# Analog_Sense.net
KiCad netlist of a schematic drawn in Altium Designer
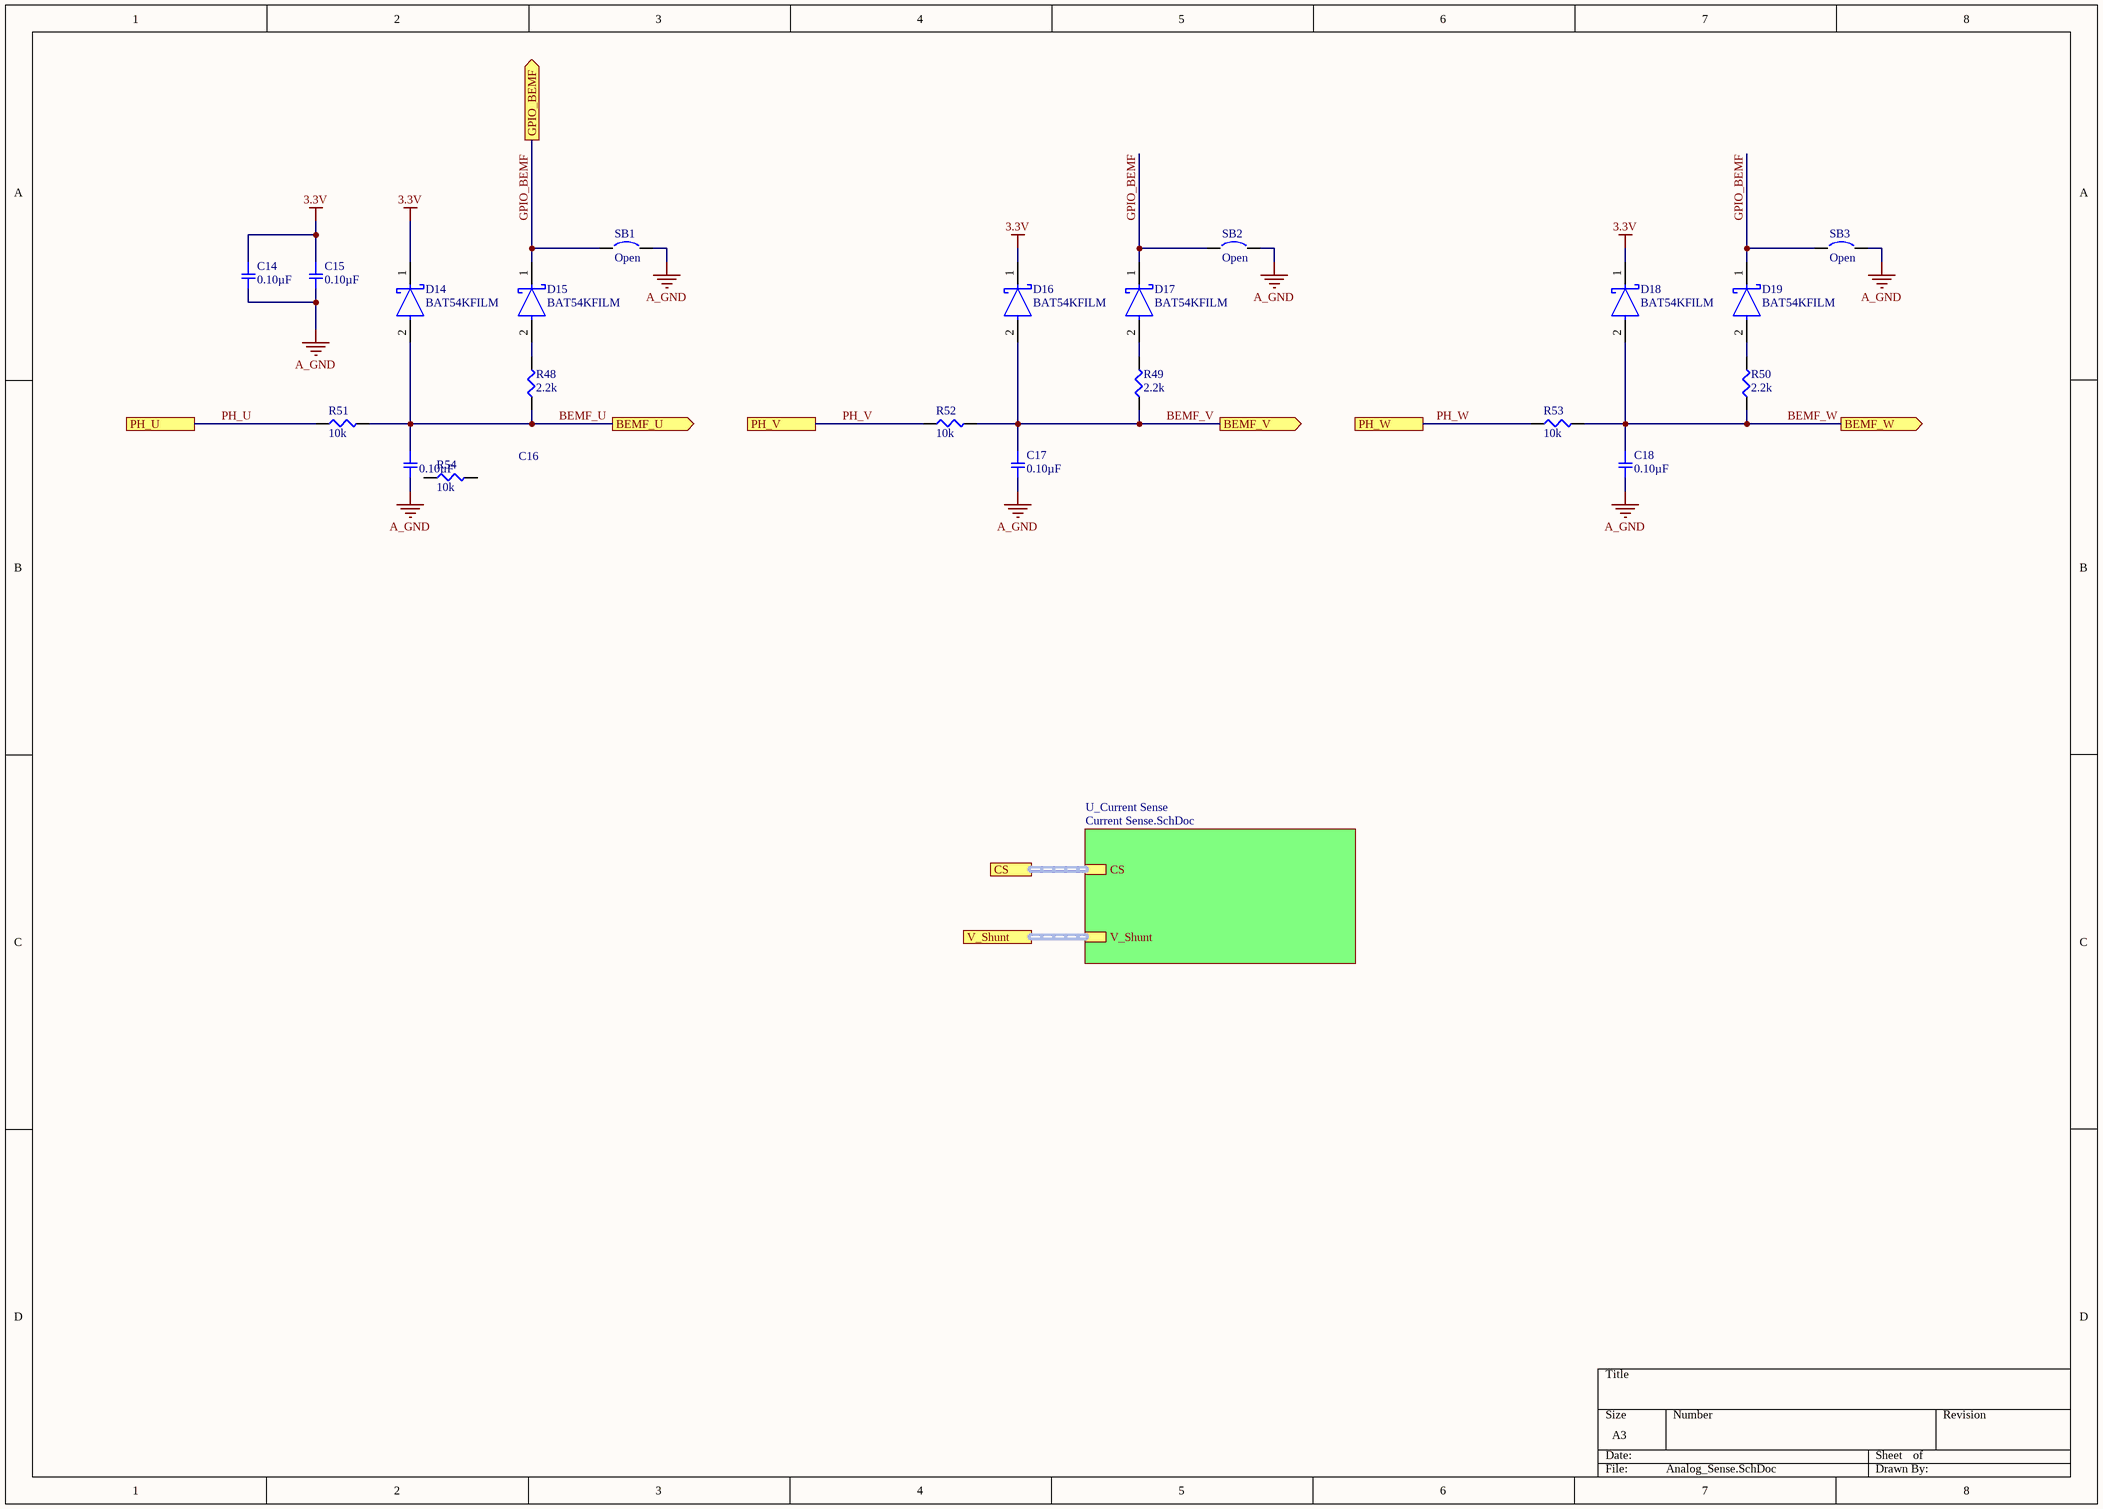
[diagram p0: Analog_Sense.SchDoc]

(export (version "E")
  (design (tool "Eeschema 10.0.6"))
  (components
    (comp (ref "C14")
      (value "0.10µF")
      (footprint "SMD-0805C")
      (description "CAP CER 0.1UF 50V X7R 0805")
      (fields
        (field (name "DIGI-KEY PART NUMBER") "490-11955-1-ND")
        (field (name "PART NUMBER") "GCD21BR71H104KA01L")
      )
      (libsource (lib "capacitor_murata_0805") (part "GCD21BR71H104KA01L"))
    )
    (comp (ref "C15")
      (value "0.10µF")
      (footprint "SMD-0805C")
      (description "CAP CER 0.1UF 50V X7R 0805")
      (fields
        (field (name "DIGI-KEY PART NUMBER") "490-11955-1-ND")
        (field (name "PART NUMBER") "GCD21BR71H104KA01L")
      )
      (libsource (lib "capacitor_murata_0805") (part "GCD21BR71H104KA01L"))
    )
    (comp (ref "C16")
      (value "0.10µF")
      (footprint "SMD-0805C")
      (description "CAP CER 0.1UF 50V X7R 0805")
      (fields
        (field (name "DIGI-KEY PART NUMBER") "490-11955-1-ND")
        (field (name "PART NUMBER") "GCD21BR71H104KA01L")
      )
      (libsource (lib "capacitor_murata_0805") (part "GCD21BR71H104KA01L"))
    )
    (comp (ref "C17")
      (value "0.10µF")
      (footprint "SMD-0805C")
      (description "CAP CER 0.1UF 50V X7R 0805")
      (fields
        (field (name "DIGI-KEY PART NUMBER") "490-11955-1-ND")
        (field (name "PART NUMBER") "GCD21BR71H104KA01L")
      )
      (libsource (lib "capacitor_murata_0805") (part "GCD21BR71H104KA01L"))
    )
    (comp (ref "C18")
      (value "0.10µF")
      (footprint "SMD-0805C")
      (description "CAP CER 0.1UF 50V X7R 0805")
      (fields
        (field (name "DIGI-KEY PART NUMBER") "490-11955-1-ND")
        (field (name "PART NUMBER") "GCD21BR71H104KA01L")
      )
      (libsource (lib "capacitor_murata_0805") (part "GCD21BR71H104KA01L"))
    )
    (comp (ref "D14")
      (value "BAT54KFILM")
      (footprint "FP-SOD-523-MFG")
      (description "DIODE SCHOTTKY 40V 300MA SOD523")
      (fields
        (field (name "OCTOPART") "https://octopart.com/bat54kfilm-stmicroelectronics-39618022")
        (field (name "MANUFACTURER") "STMicroelectronics")
      )
      (libsource (lib "Altium Content Vault") (part "1d6ec82d83fb6aee721767c19dac4b9"))
    )
    (comp (ref "D15")
      (value "BAT54KFILM")
      (footprint "FP-SOD-523-MFG")
      (description "DIODE SCHOTTKY 40V 300MA SOD523")
      (fields
        (field (name "OCTOPART") "https://octopart.com/bat54kfilm-stmicroelectronics-39618022")
        (field (name "MANUFACTURER") "STMicroelectronics")
      )
      (libsource (lib "Altium Content Vault") (part "1d6ec82d83fb6aee721767c19dac4b9"))
    )
    (comp (ref "D16")
      (value "BAT54KFILM")
      (footprint "FP-SOD-523-MFG")
      (description "DIODE SCHOTTKY 40V 300MA SOD523")
      (fields
        (field (name "OCTOPART") "https://octopart.com/bat54kfilm-stmicroelectronics-39618022")
        (field (name "MANUFACTURER") "STMicroelectronics")
      )
      (libsource (lib "Altium Content Vault") (part "1d6ec82d83fb6aee721767c19dac4b9"))
    )
    (comp (ref "D17")
      (value "BAT54KFILM")
      (footprint "FP-SOD-523-MFG")
      (description "DIODE SCHOTTKY 40V 300MA SOD523")
      (fields
        (field (name "OCTOPART") "https://octopart.com/bat54kfilm-stmicroelectronics-39618022")
        (field (name "MANUFACTURER") "STMicroelectronics")
      )
      (libsource (lib "Altium Content Vault") (part "1d6ec82d83fb6aee721767c19dac4b9"))
    )
    (comp (ref "D18")
      (value "BAT54KFILM")
      (footprint "FP-SOD-523-MFG")
      (description "DIODE SCHOTTKY 40V 300MA SOD523")
      (fields
        (field (name "OCTOPART") "https://octopart.com/bat54kfilm-stmicroelectronics-39618022")
        (field (name "MANUFACTURER") "STMicroelectronics")
      )
      (libsource (lib "Altium Content Vault") (part "1d6ec82d83fb6aee721767c19dac4b9"))
    )
    (comp (ref "D19")
      (value "BAT54KFILM")
      (footprint "FP-SOD-523-MFG")
      (description "DIODE SCHOTTKY 40V 300MA SOD523")
      (fields
        (field (name "OCTOPART") "https://octopart.com/bat54kfilm-stmicroelectronics-39618022")
        (field (name "MANUFACTURER") "STMicroelectronics")
      )
      (libsource (lib "Altium Content Vault") (part "1d6ec82d83fb6aee721767c19dac4b9"))
    )
    (comp (ref "R48")
      (value "2.2k")
      (footprint "SMD-1206-RES")
      (description "RES SMD 2.2K OHM 1% 1/4W 1206")
      (fields
        (field (name "PART NUMBER") "ERJ-8ENF2201V")
        (field (name "DIGI-KEY PART NUMBER") "P2.20KFCT-ND")
      )
      (libsource (lib "Panasonic_ERJ_1206") (part "ERJ-8ENF2201V"))
    )
    (comp (ref "R49")
      (value "2.2k")
      (footprint "SMD-1206-RES")
      (description "RES SMD 2.2K OHM 1% 1/4W 1206")
      (fields
        (field (name "PART NUMBER") "ERJ-8ENF2201V")
        (field (name "DIGI-KEY PART NUMBER") "P2.20KFCT-ND")
      )
      (libsource (lib "Panasonic_ERJ_1206") (part "ERJ-8ENF2201V"))
    )
    (comp (ref "R50")
      (value "2.2k")
      (footprint "SMD-1206-RES")
      (description "RES SMD 2.2K OHM 1% 1/4W 1206")
      (fields
        (field (name "PART NUMBER") "ERJ-8ENF2201V")
        (field (name "DIGI-KEY PART NUMBER") "P2.20KFCT-ND")
      )
      (libsource (lib "Panasonic_ERJ_1206") (part "ERJ-8ENF2201V"))
    )
    (comp (ref "R51")
      (value "10k")
      (footprint "SMD-0805-RES")
      (description "RES SMD 10K OHM 1% 1/8W 0805")
      (fields
        (field (name "PART NUMBER") "ERJ-6ENF1002V")
        (field (name "DIGI-KEY PART NUMBER") "P10.0KCCT-ND")
      )
      (libsource (lib "Panasonic_ERJ_0805") (part "ERJ-6ENF1002V"))
    )
    (comp (ref "R52")
      (value "10k")
      (footprint "SMD-0805-RES")
      (description "RES SMD 10K OHM 1% 1/8W 0805")
      (fields
        (field (name "PART NUMBER") "ERJ-6ENF1002V")
        (field (name "DIGI-KEY PART NUMBER") "P10.0KCCT-ND")
      )
      (libsource (lib "Panasonic_ERJ_0805") (part "ERJ-6ENF1002V"))
    )
    (comp (ref "R53")
      (value "10k")
      (footprint "SMD-0805-RES")
      (description "RES SMD 10K OHM 1% 1/8W 0805")
      (fields
        (field (name "PART NUMBER") "ERJ-6ENF1002V")
        (field (name "DIGI-KEY PART NUMBER") "P10.0KCCT-ND")
      )
      (libsource (lib "Panasonic_ERJ_0805") (part "ERJ-6ENF1002V"))
    )
    (comp (ref "R54")
      (value "10k")
      (footprint "SMD-0805-RES")
      (description "RES SMD 10K OHM 1% 1/8W 0805")
      (fields
        (field (name "PART NUMBER") "ERJ-6ENF1002V")
        (field (name "DIGI-KEY PART NUMBER") "P10.0KCCT-ND")
      )
      (libsource (lib "Panasonic_ERJ_0805") (part "ERJ-6ENF1002V"))
    )
    (comp (ref "SB1")
      (value "Open")
      (footprint "SB_0603")
      (description "Circuit Breaker")
      (fields (field (name "PUBLISHER") "Altium Limited"))
      (libsource (lib "NUCLEOG431RB-Custom-IN-A2212") (part "Solder Bridge"))
    )
    (comp (ref "SB2")
      (value "Open")
      (footprint "SB_0603")
      (description "Circuit Breaker")
      (fields (field (name "PUBLISHER") "Altium Limited"))
      (libsource (lib "NUCLEOG431RB-Custom-IN-A2212") (part "Solder Bridge"))
    )
    (comp (ref "SB3")
      (value "Open")
      (footprint "SB_0603")
      (description "Circuit Breaker")
      (fields (field (name "PUBLISHER") "Altium Limited"))
      (libsource (lib "NUCLEOG431RB-Custom-IN-A2212") (part "Solder Bridge"))
    )
  )
  (nets
    (net (code "3") (name "/BEMF_U") (class "Default")
      (node (ref "C16") (pin "1") (pinfunction "1_1") (pintype "passive"))
      (node (ref "D14") (pin "2") (pinfunction "A_2") (pintype "passive"))
      (node (ref "R48") (pin "1") (pinfunction "1_1") (pintype "passive"))
      (node (ref "R51") (pin "2") (pinfunction "2_2") (pintype "passive"))
    )
    (net (code "4") (name "/BEMF_V") (class "Default")
      (node (ref "C17") (pin "1") (pinfunction "1_1") (pintype "passive"))
      (node (ref "D16") (pin "2") (pinfunction "A_2") (pintype "passive"))
      (node (ref "R49") (pin "1") (pinfunction "1_1") (pintype "passive"))
      (node (ref "R52") (pin "2") (pinfunction "2_2") (pintype "passive"))
    )
    (net (code "5") (name "/BEMF_W") (class "Default")
      (node (ref "C18") (pin "1") (pinfunction "1_1") (pintype "passive"))
      (node (ref "D18") (pin "2") (pinfunction "A_2") (pintype "passive"))
      (node (ref "R50") (pin "1") (pinfunction "1_1") (pintype "passive"))
      (node (ref "R53") (pin "2") (pinfunction "2_2") (pintype "passive"))
    )
    (net (code "7") (name "/GPIO_BEMF") (class "Default")
      (node (ref "D15") (pin "1") (pinfunction "C_1") (pintype "passive"))
      (node (ref "D17") (pin "1") (pinfunction "C_1") (pintype "passive"))
      (node (ref "D19") (pin "1") (pinfunction "C_1") (pintype "passive"))
      (node (ref "SB1") (pin "1") (pinfunction "1_1") (pintype "passive"))
      (node (ref "SB2") (pin "1") (pinfunction "1_1") (pintype "passive"))
      (node (ref "SB3") (pin "1") (pinfunction "1_1") (pintype "passive"))
    )
    (net (code "8") (name "/PH_U") (class "Default")
      (node (ref "R51") (pin "1") (pinfunction "1_1") (pintype "passive"))
    )
    (net (code "9") (name "/PH_V") (class "Default")
      (node (ref "R52") (pin "1") (pinfunction "1_1") (pintype "passive"))
    )
    (net (code "10") (name "/PH_W") (class "Default")
      (node (ref "R53") (pin "1") (pinfunction "1_1") (pintype "passive"))
    )
    (net (code "12") (name "3.3V") (class "Default")
      (node (ref "C14") (pin "1") (pinfunction "1_1") (pintype "passive"))
      (node (ref "C15") (pin "1") (pinfunction "1_1") (pintype "passive"))
      (node (ref "D14") (pin "1") (pinfunction "C_1") (pintype "passive"))
      (node (ref "D16") (pin "1") (pinfunction "C_1") (pintype "passive"))
      (node (ref "D18") (pin "1") (pinfunction "C_1") (pintype "passive"))
    )
    (net (code "13") (name "A_GND") (class "Default")
      (node (ref "C14") (pin "2") (pinfunction "2_2") (pintype "passive"))
      (node (ref "C15") (pin "2") (pinfunction "2_2") (pintype "passive"))
      (node (ref "C16") (pin "2") (pinfunction "2_2") (pintype "passive"))
      (node (ref "C17") (pin "2") (pinfunction "2_2") (pintype "passive"))
      (node (ref "C18") (pin "2") (pinfunction "2_2") (pintype "passive"))
      (node (ref "SB1") (pin "2") (pinfunction "2_2") (pintype "passive"))
      (node (ref "SB2") (pin "2") (pinfunction "2_2") (pintype "passive"))
      (node (ref "SB3") (pin "2") (pinfunction "2_2") (pintype "passive"))
    )
    (net (code "14") (name "Net-(D15-A)") (class "Default")
      (node (ref "D15") (pin "2") (pinfunction "A_2") (pintype "passive"))
      (node (ref "R48") (pin "2") (pinfunction "2_2") (pintype "passive"))
    )
    (net (code "15") (name "Net-(D17-A)") (class "Default")
      (node (ref "D17") (pin "2") (pinfunction "A_2") (pintype "passive"))
      (node (ref "R49") (pin "2") (pinfunction "2_2") (pintype "passive"))
    )
    (net (code "16") (name "Net-(D19-A)") (class "Default")
      (node (ref "D19") (pin "2") (pinfunction "A_2") (pintype "passive"))
      (node (ref "R50") (pin "2") (pinfunction "2_2") (pintype "passive"))
    )
    (net (code "17") (name "unconnected-(R54-Pad1)") (class "Default")
      (node (ref "R54") (pin "1") (pinfunction "1_1") (pintype "passive"))
    )
    (net (code "18") (name "unconnected-(R54-Pad2)") (class "Default")
      (node (ref "R54") (pin "2") (pinfunction "2_2") (pintype "passive"))
    )
  )
)
